# Sample_FFC_Con_Sensor_v1.net
KiCad netlist of a schematic drawn in Altium Designer
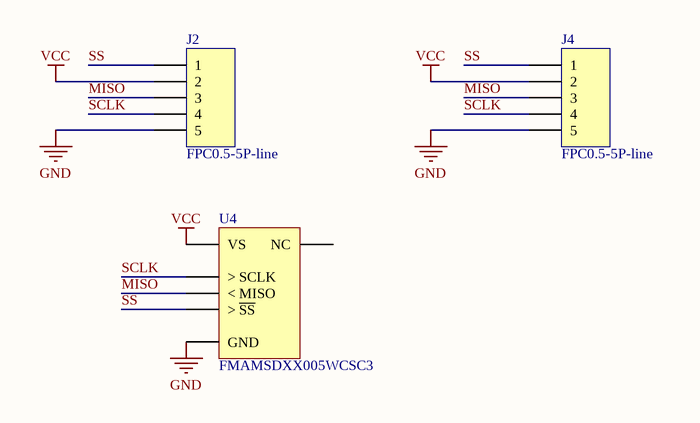
[diagram p0: Sample_FFC_Con_Sensor_v1.SchDoc]

(export (version "E")
  (design (tool "Eeschema 10.0.6"))
  (components
    (comp (ref "J2")
      (value "FPC0.5-5P-line")
      (footprint "FPC0.5-5P-Line")
      (libsource (lib "FMA_Sensor") (part "FPC0.5-5P-line"))
    )
    (comp (ref "J4")
      (value "FPC0.5-5P-line")
      (footprint "FPC0.5-5P-Line")
      (libsource (lib "FMA_Sensor") (part "FPC0.5-5P-line"))
    )
    (comp (ref "U4")
      (value "FMAMSDXX005WCSC3")
      (footprint "FMA_MICROFORCE_6-EXTENED")
      (libsource (lib "FMA_Sensor") (part "FMAMSDXX005WCSC3"))
    )
  )
  (nets
    (net (code "1") (name "/MISO") (class "Default")
      (node (ref "J2") (pin "3") (pinfunction "3_3") (pintype "passive"))
      (node (ref "J4") (pin "3") (pinfunction "3_3") (pintype "passive"))
      (node (ref "U4") (pin "5") (pinfunction "<_MISO_5") (pintype "passive"))
    )
    (net (code "2") (name "/SCLK") (class "Default")
      (node (ref "J2") (pin "4") (pinfunction "4_4") (pintype "passive"))
      (node (ref "J4") (pin "4") (pinfunction "4_4") (pintype "passive"))
      (node (ref "U4") (pin "4") (pinfunction ">_SCLK_4") (pintype "passive"))
    )
    (net (code "3") (name "/SS") (class "Default")
      (node (ref "J2") (pin "1") (pinfunction "1_1") (pintype "passive"))
      (node (ref "J4") (pin "1") (pinfunction "1_1") (pintype "passive"))
      (node (ref "U4") (pin "2") (pinfunction ">_~{SS}_2") (pintype "passive"))
    )
    (net (code "4") (name "GND") (class "Default")
      (node (ref "J2") (pin "5") (pinfunction "5_5") (pintype "passive"))
      (node (ref "J4") (pin "5") (pinfunction "5_5") (pintype "passive"))
      (node (ref "U4") (pin "3") (pinfunction "GND_3") (pintype "passive"))
    )
    (net (code "5") (name "VCC") (class "Default")
      (node (ref "J2") (pin "2") (pinfunction "2_2") (pintype "passive"))
      (node (ref "J4") (pin "2") (pinfunction "2_2") (pintype "passive"))
      (node (ref "U4") (pin "1") (pinfunction "VS_1") (pintype "passive"))
    )
    (net (code "6") (name "unconnected-(U4-NC-Pad6)") (class "Default")
      (node (ref "U4") (pin "6") (pinfunction "NC_6") (pintype "passive"))
    )
  )
)
